# design.net
KiCad netlist of a schematic drawn in EasyEDA Pro
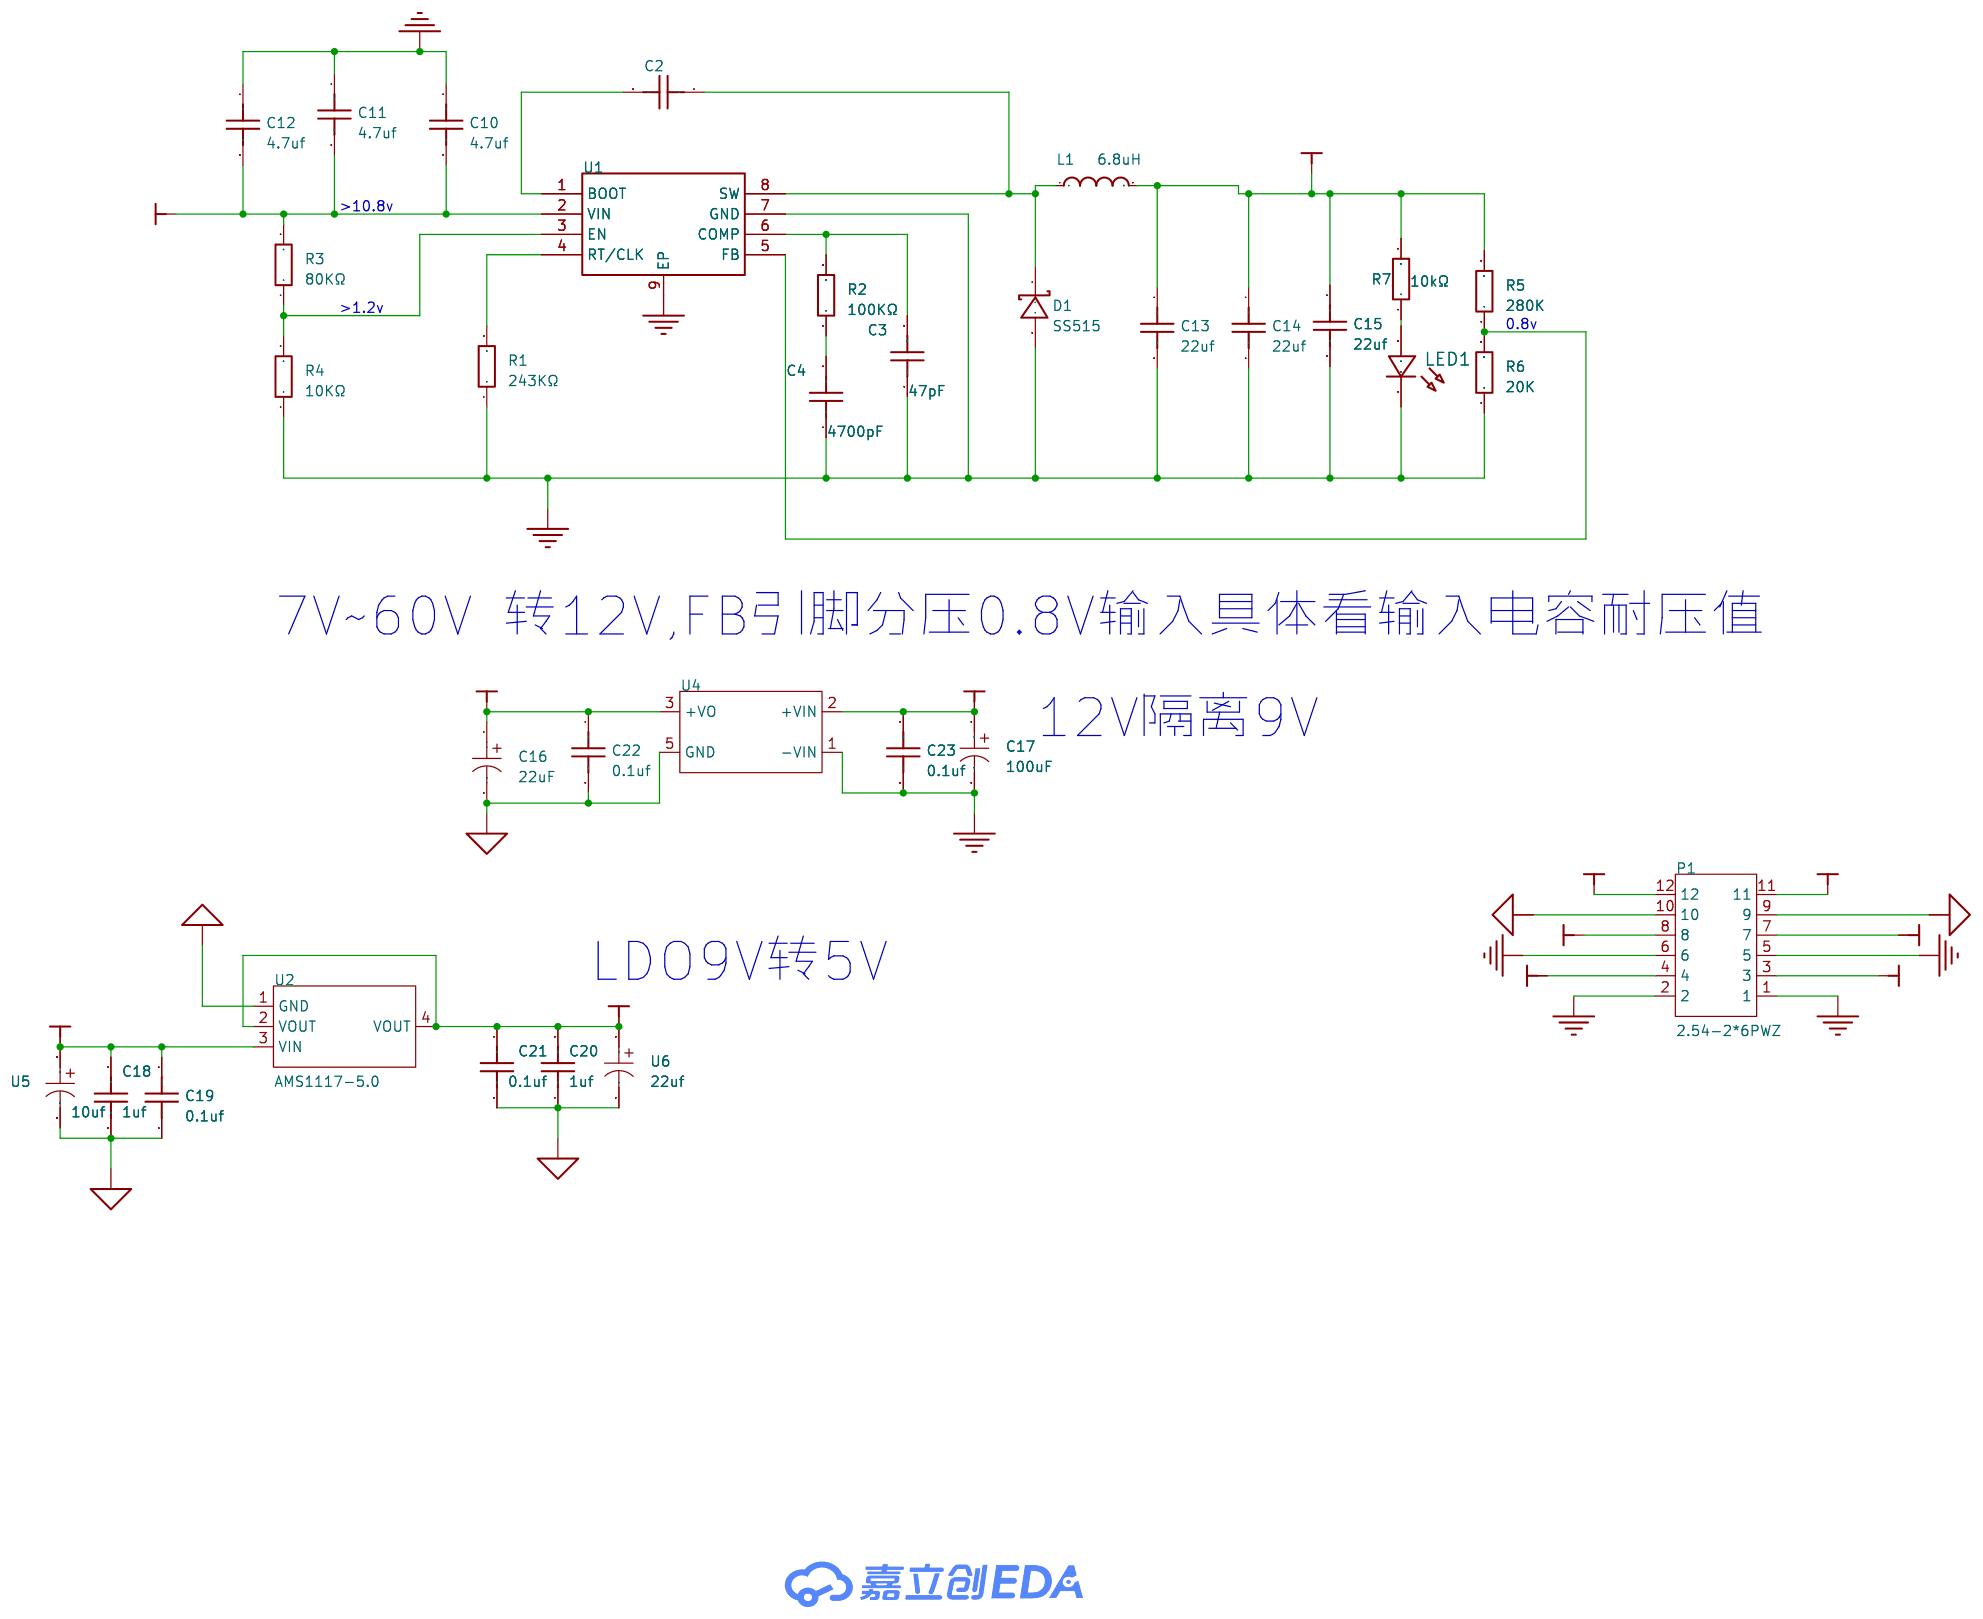
[diagram p0: schematic sheet]

(export (version "E")
  (design (tool "Eeschema 10.0.6"))
  (components
    (comp (ref "C2")
      (value "100nF")
      (footprint "easyedapro:C0603")
      (libsource (lib "easyedapro") (part "Capacitance"))
    )
    (comp (ref "C3")
      (value "47pF")
      (footprint "easyedapro:C0603")
      (libsource (lib "easyedapro") (part "Capacitance"))
    )
    (comp (ref "C4")
      (value "4700pF")
      (footprint "easyedapro:C0603")
      (libsource (lib "easyedapro") (part "Capacitance"))
    )
    (comp (ref "C10")
      (value "4.7uf")
      (footprint "easyedapro:C0603")
      (libsource (lib "easyedapro") (part "Capacitance"))
    )
    (comp (ref "C11")
      (value "4.7uf")
      (footprint "easyedapro:C0603")
      (libsource (lib "easyedapro") (part "Capacitance"))
    )
    (comp (ref "C12")
      (value "4.7uf")
      (footprint "easyedapro:C0603")
      (libsource (lib "easyedapro") (part "Capacitance"))
    )
    (comp (ref "C13")
      (value "22uf")
      (footprint "easyedapro:C0603")
      (libsource (lib "easyedapro") (part "Capacitance"))
    )
    (comp (ref "C14")
      (value "22uf")
      (footprint "easyedapro:C0603")
      (libsource (lib "easyedapro") (part "Capacitance"))
    )
    (comp (ref "C15")
      (value "22uf")
      (footprint "easyedapro:C0603")
      (libsource (lib "easyedapro") (part "Capacitance"))
    )
    (comp (ref "C16")
      (value "22uF")
      (footprint "easyedapro:CAP-TH_BD8.0-P3.50-D0.6-FD_1")
      (description "容值:22uF;精度:±20%;额定电压:160V;纹波电流:-;等效串联电阻(ESR):-;")
      (fields (field (name "Manufacturer Part") "EGW2CM220F12OT") (field (name "Manufacturer") "AISHI(艾华集团)"))
      (libsource (lib "easyedapro") (part "EGW2CM220F12OT"))
    )
    (comp (ref "C17")
      (value "100uF")
      (footprint "easyedapro:CAP-TH_BD10.0-P5.00-D0.6-FD_H16.0")
      (description "容值:100uF;精度:±20%;额定电压:100V;")
      (fields
        (field (name "Manufacturer Part") "ERA100V100M10X16")
        (field (name "Manufacturer") "JIERR(捷而瑞)")
      )
      (libsource (lib "easyedapro") (part "ERA100V100M10X16"))
    )
    (comp (ref "C18")
      (value "1uf")
      (footprint "easyedapro:C0603")
      (libsource (lib "easyedapro") (part "Capacitance"))
    )
    (comp (ref "C19")
      (value "0.1uf")
      (footprint "easyedapro:C0603")
      (libsource (lib "easyedapro") (part "Capacitance"))
    )
    (comp (ref "C20")
      (value "1uf")
      (footprint "easyedapro:C0603")
      (libsource (lib "easyedapro") (part "Capacitance"))
    )
    (comp (ref "C21")
      (value "0.1uf")
      (footprint "easyedapro:C0603")
      (libsource (lib "easyedapro") (part "Capacitance"))
    )
    (comp (ref "C22")
      (value "0.1uf")
      (footprint "easyedapro:C0603")
      (libsource (lib "easyedapro") (part "Capacitance"))
    )
    (comp (ref "C23")
      (value "0.1uf")
      (footprint "easyedapro:C0603")
      (libsource (lib "easyedapro") (part "Capacitance"))
    )
    (comp (ref "D1")
      (value "SS515")
      (footprint "easyedapro:SMA_L4.3-W2.6-LS5.2-RD")
      (description "正向压降(Vf):950mV@3A;直流反向耐压(Vr):200V;平均整流电流(Io):3A;")
      (fields (field (name "Manufacturer") "MDD"))
      (libsource (lib "easyedapro") (part "SS3200_C65001"))
    )
    (comp (ref "L1")
      (value "6.8uH")
      (footprint "easyedapro:IND-SMD_L7.1-W6.6")
      (description "电感值:10uH;精度:±20%;饱和电流(Isat):4.5A;类型:一体成型电感;")
      (fields (field (name "Manufacturer Part") "D0630HP-100MT") (field (name "Manufacturer") "DEYAN(德砚电子)"))
      (libsource (lib "easyedapro") (part "D0630HP-100MT"))
    )
    (comp (ref "LED1")
      (value "~")
      (footprint "easyedapro:LED_0603")
      (libsource (lib "easyedapro") (part "LED_R"))
    )
    (comp (ref "P1")
      (value "2.54-2*6PWZ")
      (footprint "easyedapro:HDR-TH_12P-P2.54-H-M-R2-C6-S2.54-W12.5")
      (fields (field (name "Manufacturer") "BOOMELE(博穆精密)"))
      (libsource (lib "easyedapro") (part "2*6P header"))
    )
    (comp (ref "R1")
      (value "243KΩ")
      (footprint "easyedapro:R0603")
      (libsource (lib "easyedapro") (part "电阻_1"))
    )
    (comp (ref "R2")
      (value "100KΩ")
      (footprint "easyedapro:R0603")
      (libsource (lib "easyedapro") (part "电阻_1"))
    )
    (comp (ref "R3")
      (value "80KΩ")
      (footprint "easyedapro:R0603")
      (libsource (lib "easyedapro") (part "电阻_1"))
    )
    (comp (ref "R4")
      (value "10KΩ")
      (footprint "easyedapro:R0603")
      (libsource (lib "easyedapro") (part "电阻_1"))
    )
    (comp (ref "R5")
      (value "280K")
      (footprint "easyedapro:R0603")
      (libsource (lib "easyedapro") (part "电阻_1"))
    )
    (comp (ref "R6")
      (value "20K")
      (footprint "easyedapro:R0603")
      (libsource (lib "easyedapro") (part "电阻_1"))
    )
    (comp (ref "R7")
      (value "10kΩ")
      (footprint "easyedapro:R0805")
      (description "电阻类型:厚膜电阻;阻值:5.1kΩ;精度:±1%;功率:125mW;最大工作电压:150V;温度系数:±100ppm/℃;")
      (fields
        (field (name "Manufacturer Part") "0805W8F5101T5E")
        (field (name "Manufacturer") "UNI-ROYAL(厚声)")
      )
      (libsource (lib "easyedapro") (part "0805W8F5101T5E"))
    )
    (comp (ref "U1")
      (value "TPS54560DDAR")
      (footprint "easyedapro:SOIC-8_L5.0-W4.0-P1.27-LS6.0-BL-EP2.0")
      (description "功能类型:降压型;输出类型:可调;工作电压:4.5V~60V;输出电压:800mV~58.8V;输出电流:5A;")
      (fields (field (name "Manufacturer") "TI(德州仪器)"))
      (libsource (lib "easyedapro") (part "TPS54560DDAR"))
    )
    (comp (ref "U2")
      (value "AMS1117-5.0")
      (footprint "easyedapro:SOT-223_L6.5-W3.5-P2.30-LS7.0-BR")
      (description "输出类型:固定;工作电压:15V;输出电压:5V;输出电流:1A;电源纹波抑制比(PSRR):60dB;输出极性:正极;")
      (fields (field (name "Manufacturer") "AMS"))
      (libsource (lib "easyedapro") (part "AMS1117-5.0"))
    )
    (comp (ref "U4")
      (value "250kHz")
      (footprint "easyedapro:PWRM-TH_HI-LINK_VRBXXYMD-5WR3-1")
      (fields
        (field (name "Manufacturer Part") "VRB1205YMD-5WR3")
        (field (name "Manufacturer") "HI-LINK(海凌科)")
      )
      (libsource (lib "easyedapro") (part "VRB1205YMD-5WR3"))
    )
    (comp (ref "U5")
      (value "10uf")
      (footprint "easyedapro:CAP-SMD_L3.5-W2.8-FD")
      (libsource (lib "easyedapro") (part "贴片钽电容100UF+-20%6.3VB型"))
    )
    (comp (ref "U6")
      (value "22uf")
      (footprint "easyedapro:CAP-SMD_L3.5-W2.8-FD")
      (libsource (lib "easyedapro") (part "贴片钽电容100UF+-20%6.3VB型"))
    )
  )
  (nets
    (net (code "1") (name "+5V") (class "Default")
      (node (ref "C20") (pin "1") (pinfunction "1_1") (pintype "input"))
      (node (ref "C21") (pin "1") (pinfunction "1_1") (pintype "input"))
      (node (ref "P1") (pin "11") (pinfunction "11_11") (pintype "unspecified"))
      (node (ref "P1") (pin "12") (pinfunction "12_12") (pintype "unspecified"))
      (node (ref "U2") (pin "2") (pinfunction "VOUT_2") (pintype "unspecified"))
      (node (ref "U2") (pin "4") (pinfunction "VOUT_4") (pintype "unspecified"))
      (node (ref "U6") (pin "1") (pinfunction "1_1") (pintype "input"))
    )
    (net (code "2") (name "+9V") (class "Default")
      (node (ref "C16") (pin "1") (pinfunction "1_1") (pintype "input"))
      (node (ref "C18") (pin "1") (pinfunction "1_1") (pintype "input"))
      (node (ref "C19") (pin "1") (pinfunction "1_1") (pintype "input"))
      (node (ref "C22") (pin "1") (pinfunction "1_1") (pintype "input"))
      (node (ref "U2") (pin "3") (pinfunction "VIN_3") (pintype "unspecified"))
      (node (ref "U4") (pin "3") (pinfunction "+VO_3") (pintype "unspecified"))
      (node (ref "U5") (pin "1") (pinfunction "1_1") (pintype "input"))
    )
    (net (code "3") (name "+12V") (class "Default")
      (node (ref "C13") (pin "1") (pinfunction "1_1") (pintype "input"))
      (node (ref "C14") (pin "1") (pinfunction "1_1") (pintype "input"))
      (node (ref "C15") (pin "1") (pinfunction "1_1") (pintype "input"))
      (node (ref "C17") (pin "1") (pinfunction "1_1") (pintype "input"))
      (node (ref "C23") (pin "1") (pinfunction "1_1") (pintype "input"))
      (node (ref "L1") (pin "2") (pinfunction "2_2") (pintype "unspecified"))
      (node (ref "P1") (pin "7") (pinfunction "7_7") (pintype "unspecified"))
      (node (ref "P1") (pin "8") (pinfunction "8_8") (pintype "unspecified"))
      (node (ref "R5") (pin "2") (pinfunction "2_2") (pintype "input"))
      (node (ref "R7") (pin "2") (pinfunction "2_2") (pintype "input"))
      (node (ref "U4") (pin "2") (pinfunction "+VIN_2") (pintype "unspecified"))
    )
    (net (code "4") (name "AGND") (class "Default")
      (node (ref "C16") (pin "2") (pinfunction "2_2") (pintype "input"))
      (node (ref "C18") (pin "2") (pinfunction "2_2") (pintype "input"))
      (node (ref "C19") (pin "2") (pinfunction "2_2") (pintype "input"))
      (node (ref "C20") (pin "2") (pinfunction "2_2") (pintype "input"))
      (node (ref "C21") (pin "2") (pinfunction "2_2") (pintype "input"))
      (node (ref "C22") (pin "2") (pinfunction "2_2") (pintype "input"))
      (node (ref "P1") (pin "10") (pinfunction "10_10") (pintype "unspecified"))
      (node (ref "P1") (pin "9") (pinfunction "9_9") (pintype "unspecified"))
      (node (ref "U2") (pin "1") (pinfunction "GND_1") (pintype "unspecified"))
      (node (ref "U4") (pin "5") (pinfunction "GND_5") (pintype "unspecified"))
      (node (ref "U5") (pin "2") (pinfunction "2_2") (pintype "input"))
      (node (ref "U6") (pin "2") (pinfunction "2_2") (pintype "input"))
    )
    (net (code "5") (name "GND") (class "Default")
      (node (ref "C10") (pin "1") (pinfunction "1_1") (pintype "input"))
      (node (ref "C11") (pin "1") (pinfunction "1_1") (pintype "input"))
      (node (ref "C12") (pin "1") (pinfunction "1_1") (pintype "input"))
      (node (ref "C13") (pin "2") (pinfunction "2_2") (pintype "input"))
      (node (ref "C14") (pin "2") (pinfunction "2_2") (pintype "input"))
      (node (ref "C15") (pin "2") (pinfunction "2_2") (pintype "input"))
      (node (ref "C17") (pin "2") (pinfunction "2_2") (pintype "input"))
      (node (ref "C23") (pin "2") (pinfunction "2_2") (pintype "input"))
      (node (ref "C3") (pin "1") (pinfunction "1_1") (pintype "input"))
      (node (ref "C4") (pin "1") (pinfunction "1_1") (pintype "input"))
      (node (ref "D1") (pin "2") (pinfunction "A_2") (pintype "unspecified"))
      (node (ref "LED1") (pin "1") (pinfunction "C_1") (pintype "input"))
      (node (ref "P1") (pin "1") (pinfunction "1_1") (pintype "unspecified"))
      (node (ref "P1") (pin "2") (pinfunction "2_2") (pintype "unspecified"))
      (node (ref "P1") (pin "5") (pinfunction "5_5") (pintype "unspecified"))
      (node (ref "P1") (pin "6") (pinfunction "6_6") (pintype "unspecified"))
      (node (ref "R1") (pin "1") (pinfunction "1_1") (pintype "input"))
      (node (ref "R4") (pin "1") (pinfunction "1_1") (pintype "input"))
      (node (ref "R6") (pin "1") (pinfunction "1_1") (pintype "input"))
      (node (ref "U1") (pin "7") (pinfunction "GND_7") (pintype "unspecified"))
      (node (ref "U1") (pin "9") (pinfunction "EP_9") (pintype "unspecified"))
      (node (ref "U4") (pin "1") (pinfunction "-VIN_1") (pintype "unspecified"))
    )
    (net (code "6") (name "Net-(C4-Pad2)") (class "Default")
      (node (ref "C4") (pin "2") (pinfunction "2_2") (pintype "input"))
      (node (ref "R2") (pin "1") (pinfunction "1_1") (pintype "input"))
    )
    (net (code "7") (name "Net-(D1-K)") (class "Default")
      (node (ref "C2") (pin "1") (pinfunction "1_1") (pintype "input"))
      (node (ref "D1") (pin "1") (pinfunction "K_1") (pintype "unspecified"))
      (node (ref "L1") (pin "1") (pinfunction "1_1") (pintype "unspecified"))
      (node (ref "U1") (pin "8") (pinfunction "SW_8") (pintype "unspecified"))
    )
    (net (code "8") (name "Net-(LED1-A)") (class "Default")
      (node (ref "LED1") (pin "2") (pinfunction "A_2") (pintype "input"))
      (node (ref "R7") (pin "1") (pinfunction "1_1") (pintype "input"))
    )
    (net (code "9") (name "Net-(U1-BOOT)") (class "Default")
      (node (ref "C2") (pin "2") (pinfunction "2_2") (pintype "input"))
      (node (ref "U1") (pin "1") (pinfunction "BOOT_1") (pintype "unspecified"))
    )
    (net (code "10") (name "Net-(U1-COMP)") (class "Default")
      (node (ref "C3") (pin "2") (pinfunction "2_2") (pintype "input"))
      (node (ref "R2") (pin "2") (pinfunction "2_2") (pintype "input"))
      (node (ref "U1") (pin "6") (pinfunction "COMP_6") (pintype "unspecified"))
    )
    (net (code "11") (name "Net-(U1-EN)") (class "Default")
      (node (ref "R3") (pin "1") (pinfunction "1_1") (pintype "input"))
      (node (ref "R4") (pin "2") (pinfunction "2_2") (pintype "input"))
      (node (ref "U1") (pin "3") (pinfunction "EN_3") (pintype "unspecified"))
    )
    (net (code "12") (name "Net-(U1-FB)") (class "Default")
      (node (ref "R5") (pin "1") (pinfunction "1_1") (pintype "input"))
      (node (ref "R6") (pin "2") (pinfunction "2_2") (pintype "input"))
      (node (ref "U1") (pin "5") (pinfunction "FB_5") (pintype "unspecified"))
    )
    (net (code "13") (name "Net-(U1-RT{slash}CLK)") (class "Default")
      (node (ref "R1") (pin "2") (pinfunction "2_2") (pintype "input"))
      (node (ref "U1") (pin "4") (pinfunction "RT/CLK_4") (pintype "unspecified"))
    )
    (net (code "14") (name "VCC_IN") (class "Default")
      (node (ref "C10") (pin "2") (pinfunction "2_2") (pintype "input"))
      (node (ref "C11") (pin "2") (pinfunction "2_2") (pintype "input"))
      (node (ref "C12") (pin "2") (pinfunction "2_2") (pintype "input"))
      (node (ref "P1") (pin "3") (pinfunction "3_3") (pintype "unspecified"))
      (node (ref "P1") (pin "4") (pinfunction "4_4") (pintype "unspecified"))
      (node (ref "R3") (pin "2") (pinfunction "2_2") (pintype "input"))
      (node (ref "U1") (pin "2") (pinfunction "VIN_2") (pintype "unspecified"))
    )
  )
)
